# LoginatorCore.net
KiCad netlist of a schematic drawn in EAGLE
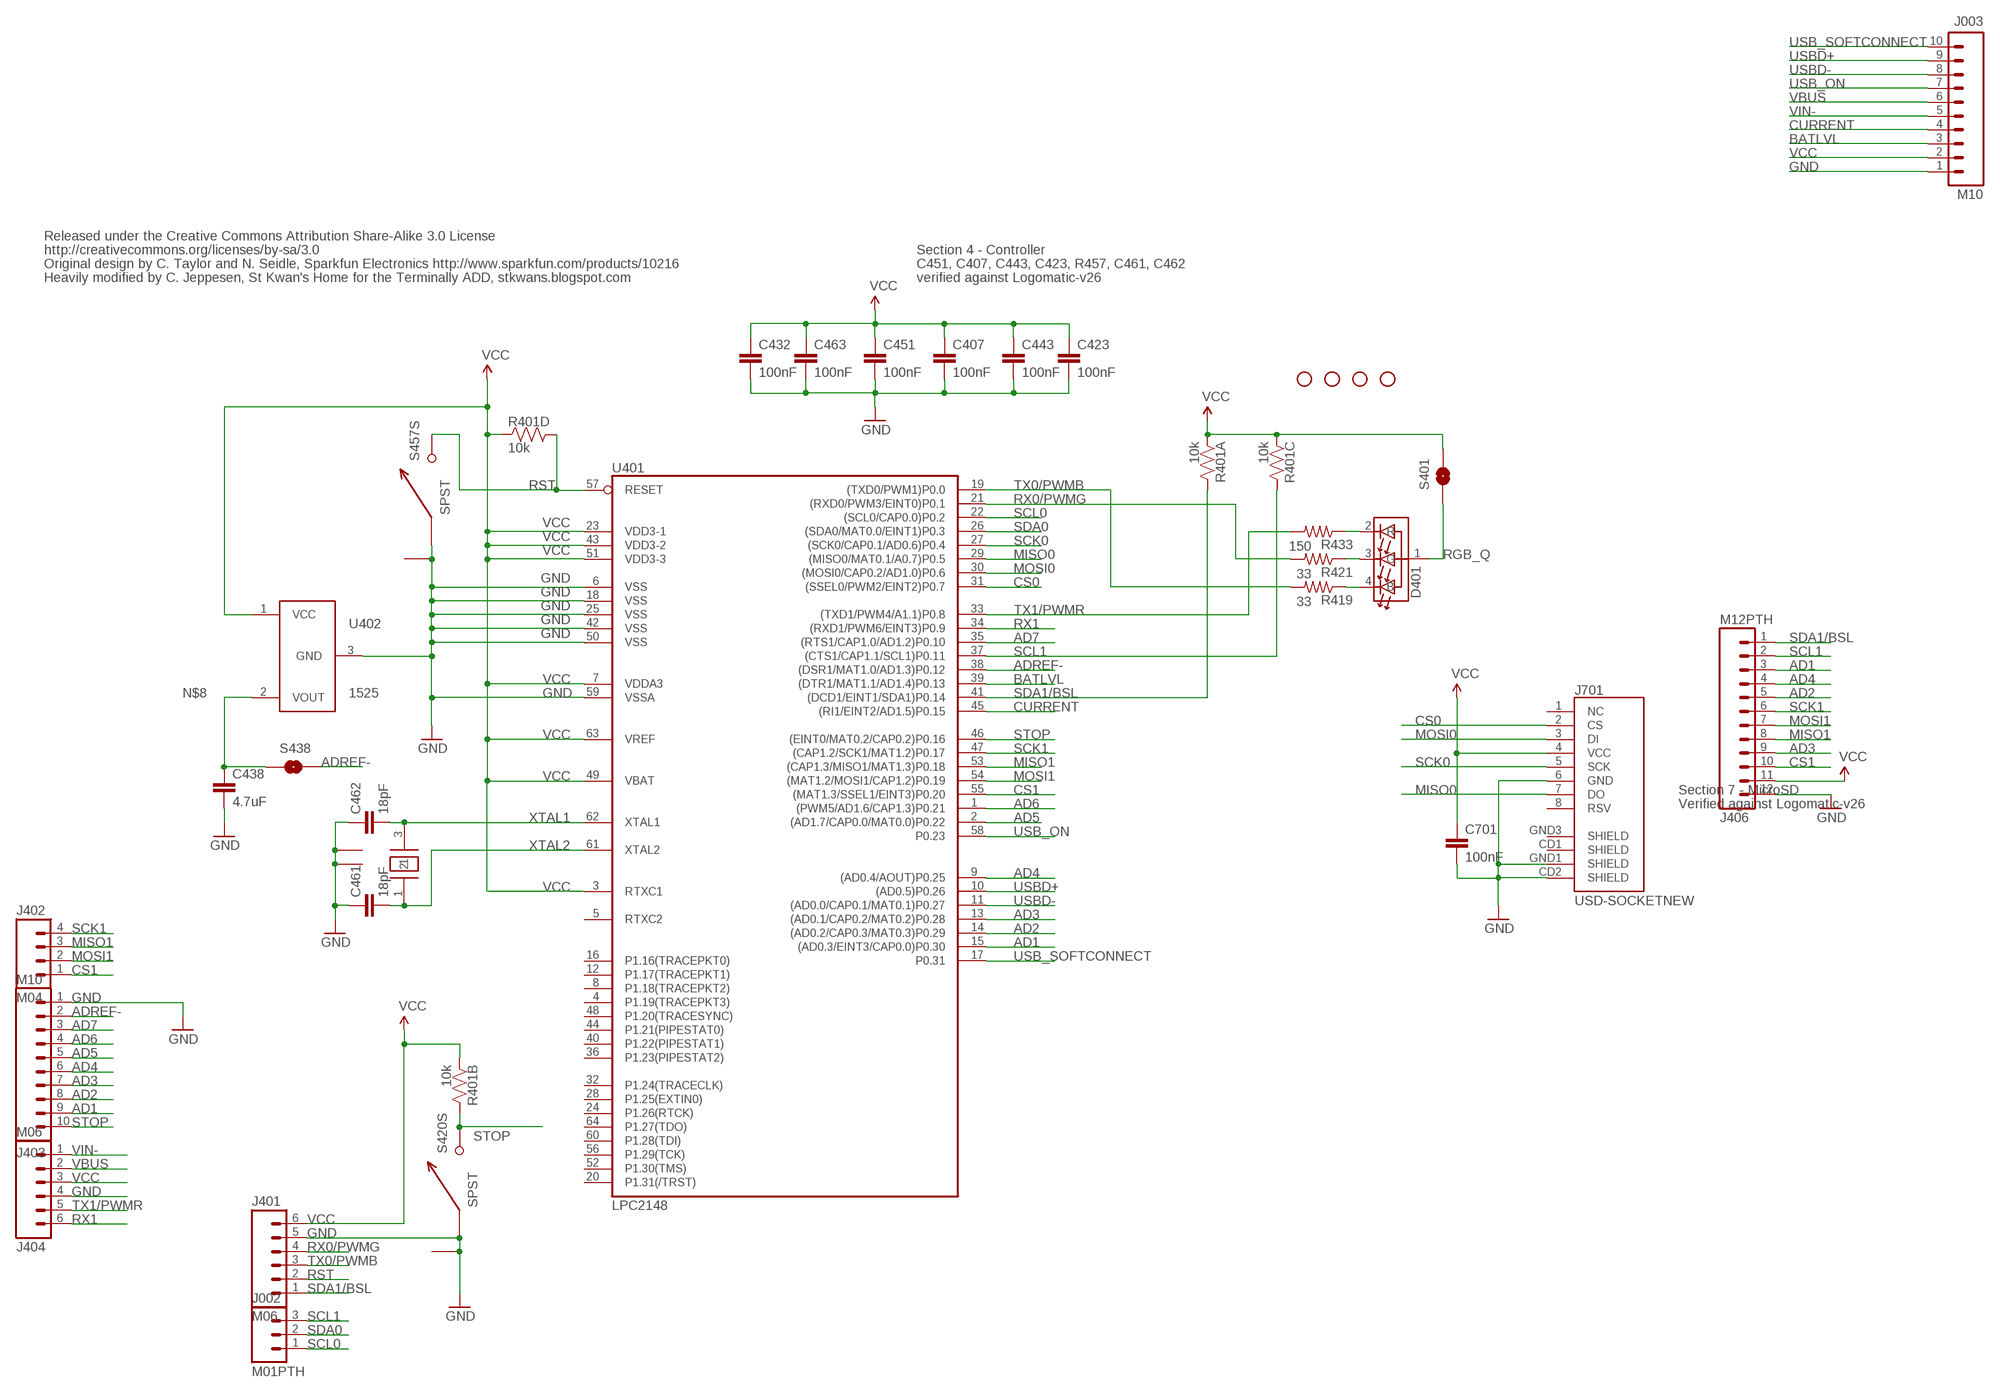
[diagram p0: schematic, sheet 1]

(export (version "E")
  (design (tool "Eeschema 10.0.6"))
  (components
    (comp (ref "C407")
      (value "100nF")
      (footprint "eagle-import:0402-CAP")
      (libsource (lib "eagle-import") (part "CAP0402-CAP"))
    )
    (comp (ref "C423")
      (value "100nF")
      (footprint "eagle-import:0402-CAP")
      (libsource (lib "eagle-import") (part "CAP0402-CAP"))
    )
    (comp (ref "C432")
      (value "100nF")
      (footprint "eagle-import:0402-CAP")
      (libsource (lib "eagle-import") (part "CAP0402-CAP"))
    )
    (comp (ref "C438")
      (value "4.7uF")
      (footprint "eagle-import:0402-CAP")
      (libsource (lib "eagle-import") (part "CAP0402-CAP"))
    )
    (comp (ref "C443")
      (value "100nF")
      (footprint "eagle-import:0402-CAP")
      (libsource (lib "eagle-import") (part "CAP0402-CAP"))
    )
    (comp (ref "C451")
      (value "100nF")
      (footprint "eagle-import:0402-CAP")
      (libsource (lib "eagle-import") (part "CAP0402-CAP"))
    )
    (comp (ref "C461")
      (value "18pF")
      (footprint "eagle-import:0402-CAP")
      (libsource (lib "eagle-import") (part "CAP0402-CAP"))
    )
    (comp (ref "C462")
      (value "18pF")
      (footprint "eagle-import:0402-CAP")
      (libsource (lib "eagle-import") (part "CAP0402-CAP"))
    )
    (comp (ref "C463")
      (value "100nF")
      (footprint "eagle-import:0402-CAP")
      (libsource (lib "eagle-import") (part "CAP0402-CAP"))
    )
    (comp (ref "C701")
      (value "100nF")
      (footprint "eagle-import:0402-CAP")
      (libsource (lib "eagle-import") (part "CAP0402-CAP"))
    )
    (comp (ref "D401")
      (value "HSMF-C118")
      (footprint "eagle-import:HSMF-C118")
      (libsource (lib "eagle-import") (part "HSMF-C118"))
    )
    (comp (ref "J002")
      (value "M01PTH")
      (footprint "eagle-import:1X03")
      (libsource (lib "eagle-import") (part "M03PTH"))
    )
    (comp (ref "J003")
      (value "M10")
      (footprint "eagle-import:1X10")
      (libsource (lib "eagle-import") (part "M10{dblquote}"))
    )
    (comp (ref "J401")
      (value "M06")
      (footprint "eagle-import:1X06")
      (libsource (lib "eagle-import") (part "M06SIP"))
    )
    (comp (ref "J402")
      (value "M04")
      (footprint "eagle-import:1X04")
      (libsource (lib "eagle-import") (part "M04PTH"))
    )
    (comp (ref "J403")
      (value "M10")
      (footprint "eagle-import:1X10")
      (libsource (lib "eagle-import") (part "M10{dblquote}"))
    )
    (comp (ref "J404")
      (value "M06")
      (footprint "eagle-import:1X06")
      (libsource (lib "eagle-import") (part "M06SIP"))
    )
    (comp (ref "J406")
      (value "M12PTH")
      (footprint "eagle-import:1X12")
      (libsource (lib "eagle-import") (part "M12PTH"))
    )
    (comp (ref "J701")
      (value "USD-SOCKETNEW")
      (footprint "eagle-import:MICRO-SD-SOCKET-PP")
      (libsource (lib "eagle-import") (part "USD-SOCKETNEW"))
    )
    (comp (ref "JP1")
      (value "STAND-OFF")
      (footprint "eagle-import:STAND-OFF")
      (libsource (lib "eagle-import") (part "STAND-OFF"))
    )
    (comp (ref "JP2")
      (value "STAND-OFF")
      (footprint "eagle-import:STAND-OFF")
      (libsource (lib "eagle-import") (part "STAND-OFF"))
    )
    (comp (ref "JP3")
      (value "STAND-OFF")
      (footprint "eagle-import:STAND-OFF")
      (libsource (lib "eagle-import") (part "STAND-OFF"))
    )
    (comp (ref "JP4")
      (value "STAND-OFF")
      (footprint "eagle-import:STAND-OFF")
      (libsource (lib "eagle-import") (part "STAND-OFF"))
    )
    (comp (ref "R401")
      (value "10k")
      (footprint "eagle-import:CRA04")
      (libsource (lib "eagle-import") (part "RP404"))
    )
    (comp (ref "R419")
      (value "33")
      (footprint "eagle-import:0402-RES")
      (libsource (lib "eagle-import") (part "RESISTOR0402-RES"))
    )
    (comp (ref "R421")
      (value "33")
      (footprint "eagle-import:0402-RES")
      (libsource (lib "eagle-import") (part "RESISTOR0402-RES"))
    )
    (comp (ref "R433")
      (value "150")
      (footprint "eagle-import:0402-RES")
      (libsource (lib "eagle-import") (part "RESISTOR0402-RES"))
    )
    (comp (ref "S401")
      (value "SOLDERJUMPERNO")
      (footprint "eagle-import:SJ_2S-NO")
      (libsource (lib "eagle-import") (part "SOLDERJUMPERNO"))
    )
    (comp (ref "S420")
      (value "SPST")
      (footprint "eagle-import:B3U-1100P")
      (libsource (lib "eagle-import") (part "B3U-1100P"))
    )
    (comp (ref "S438")
      (value "SOLDERJUMPERNO")
      (footprint "eagle-import:SJ_2S-NO")
      (libsource (lib "eagle-import") (part "SOLDERJUMPERNO"))
    )
    (comp (ref "S457")
      (value "SPST")
      (footprint "eagle-import:B3U-1100P")
      (libsource (lib "eagle-import") (part "B3U-1100P"))
    )
    (comp (ref "U401")
      (value "LPC2148")
      (footprint "eagle-import:SQFP-S-10X10-64")
      (libsource (lib "eagle-import") (part "LPC213X"))
    )
    (comp (ref "U402")
      (value "1525")
      (footprint "eagle-import:SOT-23-3")
      (libsource (lib "eagle-import") (part "MCP1525"))
    )
    (comp (ref "Y401")
      (value "12M")
      (footprint "eagle-import:CRYSTAL_SMD")
      (libsource (lib "eagle-import") (part "TSX-3225"))
    )
  )
  (nets
    (net (code "1") (name "/AD1") (class "Default")
      (node (ref "J403") (pin "9") (pinfunction "9_9") (pintype "passive"))
      (node (ref "J406") (pin "3") (pinfunction "3_3") (pintype "passive"))
      (node (ref "U401") (pin "15") (pinfunction "(AD0.3/EINT3/CAP0.0)P0.30_15") (pintype "bidirectional"))
    )
    (net (code "2") (name "/AD2") (class "Default")
      (node (ref "J403") (pin "8") (pinfunction "8_8") (pintype "passive"))
      (node (ref "J406") (pin "5") (pinfunction "5_5") (pintype "passive"))
      (node (ref "U401") (pin "14") (pinfunction "(AD0.2/CAP0.3/MAT0.3)P0.29_14") (pintype "bidirectional"))
    )
    (net (code "3") (name "/AD3") (class "Default")
      (node (ref "J403") (pin "7") (pinfunction "7_7") (pintype "passive"))
      (node (ref "J406") (pin "9") (pinfunction "9_9") (pintype "passive"))
      (node (ref "U401") (pin "13") (pinfunction "(AD0.1/CAP0.2/MAT0.2)P0.28_13") (pintype "bidirectional"))
    )
    (net (code "4") (name "/AD4") (class "Default")
      (node (ref "J403") (pin "6") (pinfunction "6_6") (pintype "passive"))
      (node (ref "J406") (pin "4") (pinfunction "4_4") (pintype "passive"))
      (node (ref "U401") (pin "9") (pinfunction "(AD0.4/AOUT)P0.25_9") (pintype "bidirectional"))
    )
    (net (code "5") (name "/AD5") (class "Default")
      (node (ref "J403") (pin "5") (pinfunction "5_5") (pintype "passive"))
      (node (ref "U401") (pin "2") (pinfunction "(AD1.7/CAP0.0/MAT0.0)P0.22_2") (pintype "bidirectional"))
    )
    (net (code "6") (name "/AD6") (class "Default")
      (node (ref "J403") (pin "4") (pinfunction "4_4") (pintype "passive"))
      (node (ref "U401") (pin "1") (pinfunction "(PWM5/AD1.6/CAP1.3)P0.21_1") (pintype "bidirectional"))
    )
    (net (code "7") (name "/AD7") (class "Default")
      (node (ref "J403") (pin "3") (pinfunction "3_3") (pintype "passive"))
      (node (ref "U401") (pin "35") (pinfunction "(RTS1/CAP1.0/AD1.2)P0.10_35") (pintype "bidirectional"))
    )
    (net (code "8") (name "/ADREF-") (class "Default")
      (node (ref "J403") (pin "2") (pinfunction "2_2") (pintype "passive"))
      (node (ref "S438") (pin "2") (pinfunction "2_2") (pintype "passive"))
      (node (ref "U401") (pin "38") (pinfunction "(DSR1/MAT1.0/AD1.3)P0.12_38") (pintype "bidirectional"))
    )
    (net (code "9") (name "/BATLVL") (class "Default")
      (node (ref "J003") (pin "3") (pinfunction "3_3") (pintype "passive"))
      (node (ref "U401") (pin "39") (pinfunction "(DTR1/MAT1.1/AD1.4)P0.13_39") (pintype "bidirectional"))
    )
    (net (code "10") (name "/CS0") (class "Default")
      (node (ref "J701") (pin "2") (pinfunction "CS_2") (pintype "bidirectional"))
      (node (ref "U401") (pin "31") (pinfunction "(SSEL0/PWM2/EINT2)P0.7_31") (pintype "bidirectional"))
    )
    (net (code "11") (name "/CS1") (class "Default")
      (node (ref "J402") (pin "1") (pinfunction "1_1") (pintype "passive"))
      (node (ref "J406") (pin "10") (pinfunction "10_10") (pintype "passive"))
      (node (ref "U401") (pin "55") (pinfunction "(MAT1.3/SSEL1/EINT3)P0.20_55") (pintype "bidirectional"))
    )
    (net (code "12") (name "/CURRENT") (class "Default")
      (node (ref "J003") (pin "4") (pinfunction "4_4") (pintype "passive"))
      (node (ref "U401") (pin "45") (pinfunction "(RI1/EINT2/AD1.5)P0.15_45") (pintype "bidirectional"))
    )
    (net (code "13") (name "/MISO0") (class "Default")
      (node (ref "J701") (pin "7") (pinfunction "DO_7") (pintype "bidirectional"))
      (node (ref "U401") (pin "29") (pinfunction "(MISO0/MAT0.1/A0.7)P0.5_29") (pintype "bidirectional"))
    )
    (net (code "14") (name "/MISO1") (class "Default")
      (node (ref "J402") (pin "3") (pinfunction "3_3") (pintype "passive"))
      (node (ref "J406") (pin "8") (pinfunction "8_8") (pintype "passive"))
      (node (ref "U401") (pin "53") (pinfunction "(CAP1.3/MISO1/MAT1.3)P0.18_53") (pintype "bidirectional"))
    )
    (net (code "15") (name "/MOSI0") (class "Default")
      (node (ref "J701") (pin "3") (pinfunction "DI_3") (pintype "bidirectional"))
      (node (ref "U401") (pin "30") (pinfunction "(MOSI0/CAP0.2/AD1.0)P0.6_30") (pintype "bidirectional"))
    )
    (net (code "16") (name "/MOSI1") (class "Default")
      (node (ref "J402") (pin "2") (pinfunction "2_2") (pintype "passive"))
      (node (ref "J406") (pin "7") (pinfunction "7_7") (pintype "passive"))
      (node (ref "U401") (pin "54") (pinfunction "(MAT1.2/MOSI1/CAP1.2)P0.19_54") (pintype "bidirectional"))
    )
    (net (code "17") (name "/N$8") (class "Default")
      (node (ref "C438") (pin "1") (pinfunction "1_1") (pintype "passive"))
      (node (ref "S438") (pin "1") (pinfunction "1_1") (pintype "passive"))
      (node (ref "U402") (pin "2") (pinfunction "VOUT_2") (pintype "bidirectional"))
    )
    (net (code "18") (name "/RGB_Q") (class "Default")
      (node (ref "D401") (pin "1") (pinfunction "A_1") (pintype "passive"))
      (node (ref "S401") (pin "1") (pinfunction "1_1") (pintype "passive"))
    )
    (net (code "19") (name "/RST") (class "Default")
      (node (ref "J401") (pin "2") (pinfunction "2_2") (pintype "passive"))
      (node (ref "R401") (pin "5") (pinfunction "2_5") (pintype "passive"))
      (node (ref "S457") (pin "P$2") (pinfunction "2_P$2") (pintype "bidirectional"))
      (node (ref "U401") (pin "57") (pinfunction "RESET_57") (pintype "input"))
    )
    (net (code "20") (name "/RX0{slash}PWMG") (class "Default")
      (node (ref "J401") (pin "4") (pinfunction "4_4") (pintype "passive"))
      (node (ref "R421") (pin "2") (pinfunction "2_2") (pintype "passive"))
      (node (ref "U401") (pin "21") (pinfunction "(RXD0/PWM3/EINT0)P0.1_21") (pintype "bidirectional"))
    )
    (net (code "21") (name "/RX1") (class "Default")
      (node (ref "J404") (pin "6") (pinfunction "6_6") (pintype "passive"))
      (node (ref "U401") (pin "34") (pinfunction "(RXD1/PWM6/EINT3)P0.9_34") (pintype "bidirectional"))
    )
    (net (code "22") (name "/SCK0") (class "Default")
      (node (ref "J701") (pin "5") (pinfunction "SCK_5") (pintype "bidirectional"))
      (node (ref "U401") (pin "27") (pinfunction "(SCK0/CAP0.1/AD0.6)P0.4_27") (pintype "bidirectional"))
    )
    (net (code "23") (name "/SCK1") (class "Default")
      (node (ref "J402") (pin "4") (pinfunction "4_4") (pintype "passive"))
      (node (ref "J406") (pin "6") (pinfunction "6_6") (pintype "passive"))
      (node (ref "U401") (pin "47") (pinfunction "(CAP1.2/SCK1/MAT1.2)P0.17_47") (pintype "bidirectional"))
    )
    (net (code "24") (name "/SCL0") (class "Default")
      (node (ref "J002") (pin "1") (pinfunction "1_1") (pintype "passive"))
      (node (ref "U401") (pin "22") (pinfunction "(SCL0/CAP0.0)P0.2_22") (pintype "bidirectional"))
    )
    (net (code "25") (name "/SCL1") (class "Default")
      (node (ref "J002") (pin "3") (pinfunction "3_3") (pintype "passive"))
      (node (ref "J406") (pin "2") (pinfunction "2_2") (pintype "passive"))
      (node (ref "R401") (pin "6") (pinfunction "2_6") (pintype "passive"))
      (node (ref "U401") (pin "37") (pinfunction "(CTS1/CAP1.1/SCL1)P0.11_37") (pintype "bidirectional"))
    )
    (net (code "26") (name "/SDA0") (class "Default")
      (node (ref "J002") (pin "2") (pinfunction "2_2") (pintype "passive"))
      (node (ref "U401") (pin "26") (pinfunction "(SDA0/MAT0.0/EINT1)P0.3_26") (pintype "bidirectional"))
    )
    (net (code "27") (name "/SDA1{slash}BSL") (class "Default")
      (node (ref "J401") (pin "1") (pinfunction "1_1") (pintype "passive"))
      (node (ref "J406") (pin "1") (pinfunction "1_1") (pintype "passive"))
      (node (ref "R401") (pin "8") (pinfunction "2_8") (pintype "passive"))
      (node (ref "U401") (pin "41") (pinfunction "(DCD1/EINT1/SDA1)P0.14_41") (pintype "bidirectional"))
    )
    (net (code "28") (name "/STOP") (class "Default")
      (node (ref "J403") (pin "10") (pinfunction "10_10") (pintype "passive"))
      (node (ref "R401") (pin "7") (pinfunction "2_7") (pintype "passive"))
      (node (ref "S420") (pin "P$2") (pinfunction "2_P$2") (pintype "bidirectional"))
      (node (ref "U401") (pin "46") (pinfunction "(EINT0/MAT0.2/CAP0.2)P0.16_46") (pintype "bidirectional"))
    )
    (net (code "29") (name "/TX0{slash}PWMB") (class "Default")
      (node (ref "J401") (pin "3") (pinfunction "3_3") (pintype "passive"))
      (node (ref "R419") (pin "2") (pinfunction "2_2") (pintype "passive"))
      (node (ref "U401") (pin "19") (pinfunction "(TXD0/PWM1)P0.0_19") (pintype "bidirectional"))
    )
    (net (code "30") (name "/TX1{slash}PWMR") (class "Default")
      (node (ref "J404") (pin "5") (pinfunction "5_5") (pintype "passive"))
      (node (ref "R433") (pin "2") (pinfunction "2_2") (pintype "passive"))
      (node (ref "U401") (pin "33") (pinfunction "(TXD1/PWM4/A1.1)P0.8_33") (pintype "bidirectional"))
    )
    (net (code "31") (name "/USBD+") (class "Default")
      (node (ref "J003") (pin "9") (pinfunction "9_9") (pintype "passive"))
      (node (ref "U401") (pin "10") (pinfunction "(AD0.5)P0.26_10") (pintype "bidirectional"))
    )
    (net (code "32") (name "/USBD-") (class "Default")
      (node (ref "J003") (pin "8") (pinfunction "8_8") (pintype "passive"))
      (node (ref "U401") (pin "11") (pinfunction "(AD0.0/CAP0.1/MAT0.1)P0.27_11") (pintype "bidirectional"))
    )
    (net (code "33") (name "/USB_ON") (class "Default")
      (node (ref "J003") (pin "7") (pinfunction "7_7") (pintype "passive"))
      (node (ref "U401") (pin "58") (pinfunction "P0.23_58") (pintype "bidirectional"))
    )
    (net (code "34") (name "/USB_SOFTCONNECT") (class "Default")
      (node (ref "J003") (pin "10") (pinfunction "10_10") (pintype "passive"))
      (node (ref "U401") (pin "17") (pinfunction "P0.31_17") (pintype "output"))
    )
    (net (code "35") (name "/VBUS") (class "Default")
      (node (ref "J003") (pin "6") (pinfunction "6_6") (pintype "passive"))
      (node (ref "J404") (pin "2") (pinfunction "2_2") (pintype "passive"))
    )
    (net (code "36") (name "/VIN-") (class "Default")
      (node (ref "J003") (pin "5") (pinfunction "5_5") (pintype "passive"))
      (node (ref "J404") (pin "1") (pinfunction "1_1") (pintype "passive"))
    )
    (net (code "37") (name "/XTAL1") (class "Default")
      (node (ref "C462") (pin "2") (pinfunction "2_2") (pintype "passive"))
      (node (ref "U401") (pin "62") (pinfunction "XTAL1_62") (pintype "input"))
      (node (ref "Y401") (pin "3") (pinfunction "2_3") (pintype "bidirectional"))
    )
    (net (code "38") (name "/XTAL2") (class "Default")
      (node (ref "C461") (pin "2") (pinfunction "2_2") (pintype "passive"))
      (node (ref "U401") (pin "61") (pinfunction "XTAL2_61") (pintype "output"))
      (node (ref "Y401") (pin "1") (pinfunction "1_1") (pintype "bidirectional"))
    )
    (net (code "39") (name "GND") (class "Default")
      (node (ref "C407") (pin "2") (pinfunction "2_2") (pintype "passive"))
      (node (ref "C423") (pin "2") (pinfunction "2_2") (pintype "passive"))
      (node (ref "C432") (pin "2") (pinfunction "2_2") (pintype "passive"))
      (node (ref "C438") (pin "2") (pinfunction "2_2") (pintype "passive"))
      (node (ref "C443") (pin "2") (pinfunction "2_2") (pintype "passive"))
      (node (ref "C451") (pin "2") (pinfunction "2_2") (pintype "passive"))
      (node (ref "C461") (pin "1") (pinfunction "1_1") (pintype "passive"))
      (node (ref "C462") (pin "1") (pinfunction "1_1") (pintype "passive"))
      (node (ref "C463") (pin "2") (pinfunction "2_2") (pintype "passive"))
      (node (ref "C701") (pin "2") (pinfunction "2_2") (pintype "passive"))
      (node (ref "J003") (pin "1") (pinfunction "1_1") (pintype "passive"))
      (node (ref "J401") (pin "5") (pinfunction "5_5") (pintype "passive"))
      (node (ref "J403") (pin "1") (pinfunction "1_1") (pintype "passive"))
      (node (ref "J404") (pin "4") (pinfunction "4_4") (pintype "passive"))
      (node (ref "J406") (pin "12") (pinfunction "12_12") (pintype "passive"))
      (node (ref "J701") (pin "6") (pinfunction "GND_6") (pintype "bidirectional"))
      (node (ref "J701") (pin "CD2") (pinfunction "SHIELD_CD2") (pintype "bidirectional"))
      (node (ref "J701") (pin "GND1") (pinfunction "SHIELD_GND1") (pintype "bidirectional"))
      (node (ref "S420") (pin "P$1") (pinfunction "1_P$1") (pintype "bidirectional"))
      (node (ref "S420") (pin "P$3") (pinfunction "1_P$3") (pintype "bidirectional"))
      (node (ref "S457") (pin "P$1") (pinfunction "1_P$1") (pintype "bidirectional"))
      (node (ref "S457") (pin "P$3") (pinfunction "1_P$3") (pintype "bidirectional"))
      (node (ref "U401") (pin "18") (pinfunction "VSS_18") (pintype "power_in"))
      (node (ref "U401") (pin "25") (pinfunction "VSS_25") (pintype "power_in"))
      (node (ref "U401") (pin "42") (pinfunction "VSS_42") (pintype "power_in"))
      (node (ref "U401") (pin "50") (pinfunction "VSS_50") (pintype "power_in"))
      (node (ref "U401") (pin "59") (pinfunction "VSSA_59") (pintype "power_in"))
      (node (ref "U401") (pin "6") (pinfunction "VSS_6") (pintype "power_in"))
      (node (ref "U402") (pin "3") (pinfunction "GND_3") (pintype "bidirectional"))
      (node (ref "Y401") (pin "2") (pinfunction "1_2") (pintype "bidirectional"))
      (node (ref "Y401") (pin "4") (pinfunction "1_4") (pintype "bidirectional"))
    )
    (net (code "40") (name "Net-(D401-B)") (class "Default")
      (node (ref "D401") (pin "4") (pinfunction "B_4") (pintype "passive"))
      (node (ref "R419") (pin "1") (pinfunction "1_1") (pintype "passive"))
    )
    (net (code "41") (name "Net-(D401-G)") (class "Default")
      (node (ref "D401") (pin "3") (pinfunction "G_3") (pintype "passive"))
      (node (ref "R421") (pin "1") (pinfunction "1_1") (pintype "passive"))
    )
    (net (code "42") (name "Net-(D401-R)") (class "Default")
      (node (ref "D401") (pin "2") (pinfunction "R_2") (pintype "passive"))
      (node (ref "R433") (pin "1") (pinfunction "1_1") (pintype "passive"))
    )
    (net (code "43") (name "VCC") (class "Default")
      (node (ref "C407") (pin "1") (pinfunction "1_1") (pintype "passive"))
      (node (ref "C423") (pin "1") (pinfunction "1_1") (pintype "passive"))
      (node (ref "C432") (pin "1") (pinfunction "1_1") (pintype "passive"))
      (node (ref "C443") (pin "1") (pinfunction "1_1") (pintype "passive"))
      (node (ref "C451") (pin "1") (pinfunction "1_1") (pintype "passive"))
      (node (ref "C463") (pin "1") (pinfunction "1_1") (pintype "passive"))
      (node (ref "C701") (pin "1") (pinfunction "1_1") (pintype "passive"))
      (node (ref "J003") (pin "2") (pinfunction "2_2") (pintype "passive"))
      (node (ref "J401") (pin "6") (pinfunction "6_6") (pintype "passive"))
      (node (ref "J404") (pin "3") (pinfunction "3_3") (pintype "passive"))
      (node (ref "J406") (pin "11") (pinfunction "11_11") (pintype "passive"))
      (node (ref "J701") (pin "4") (pinfunction "VCC_4") (pintype "bidirectional"))
      (node (ref "R401") (pin "1") (pinfunction "1_1") (pintype "passive"))
      (node (ref "R401") (pin "2") (pinfunction "1_2") (pintype "passive"))
      (node (ref "R401") (pin "3") (pinfunction "1_3") (pintype "passive"))
      (node (ref "R401") (pin "4") (pinfunction "1_4") (pintype "passive"))
      (node (ref "S401") (pin "2") (pinfunction "2_2") (pintype "passive"))
      (node (ref "U401") (pin "23") (pinfunction "VDD3-1_23") (pintype "power_in"))
      (node (ref "U401") (pin "3") (pinfunction "RTXC1_3") (pintype "input"))
      (node (ref "U401") (pin "43") (pinfunction "VDD3-2_43") (pintype "power_in"))
      (node (ref "U401") (pin "49") (pinfunction "VBAT_49") (pintype "power_in"))
      (node (ref "U401") (pin "51") (pinfunction "VDD3-3_51") (pintype "power_in"))
      (node (ref "U401") (pin "63") (pinfunction "VREF_63") (pintype "input"))
      (node (ref "U401") (pin "7") (pinfunction "VDDA3_7") (pintype "power_in"))
      (node (ref "U402") (pin "1") (pinfunction "VCC_1") (pintype "bidirectional"))
    )
    (net (code "44") (name "unconnected-(J701-NC-Pad1)") (class "Default")
      (node (ref "J701") (pin "1") (pinfunction "NC_1") (pintype "bidirectional"))
    )
    (net (code "45") (name "unconnected-(J701-RSV-Pad8)") (class "Default")
      (node (ref "J701") (pin "8") (pinfunction "RSV_8") (pintype "bidirectional"))
    )
    (net (code "46") (name "unconnected-(J701-SHIELD-PadCD1)") (class "Default")
      (node (ref "J701") (pin "CD1") (pinfunction "SHIELD_CD1") (pintype "bidirectional"))
    )
    (net (code "47") (name "unconnected-(J701-SHIELD-PadGND3)") (class "Default")
      (node (ref "J701") (pin "GND3") (pinfunction "SHIELD_GND3") (pintype "bidirectional"))
    )
    (net (code "48") (name "unconnected-(U401-P1.16(TRACEPKT0)-Pad16)") (class "Default")
      (node (ref "U401") (pin "16") (pinfunction "P1.16(TRACEPKT0)_16") (pintype "bidirectional"))
    )
    (net (code "49") (name "unconnected-(U401-P1.17(TRACEPKT1)-Pad12)") (class "Default")
      (node (ref "U401") (pin "12") (pinfunction "P1.17(TRACEPKT1)_12") (pintype "bidirectional"))
    )
    (net (code "50") (name "unconnected-(U401-P1.18(TRACEPKT2)-Pad8)") (class "Default")
      (node (ref "U401") (pin "8") (pinfunction "P1.18(TRACEPKT2)_8") (pintype "bidirectional"))
    )
    (net (code "51") (name "unconnected-(U401-P1.19(TRACEPKT3)-Pad4)") (class "Default")
      (node (ref "U401") (pin "4") (pinfunction "P1.19(TRACEPKT3)_4") (pintype "bidirectional"))
    )
    (net (code "52") (name "unconnected-(U401-P1.20(TRACESYNC)-Pad48)") (class "Default")
      (node (ref "U401") (pin "48") (pinfunction "P1.20(TRACESYNC)_48") (pintype "bidirectional"))
    )
    (net (code "53") (name "unconnected-(U401-P1.21(PIPESTAT0)-Pad44)") (class "Default")
      (node (ref "U401") (pin "44") (pinfunction "P1.21(PIPESTAT0)_44") (pintype "bidirectional"))
    )
    (net (code "54") (name "unconnected-(U401-P1.22(PIPESTAT1)-Pad40)") (class "Default")
      (node (ref "U401") (pin "40") (pinfunction "P1.22(PIPESTAT1)_40") (pintype "bidirectional"))
    )
    (net (code "55") (name "unconnected-(U401-P1.23(PIPESTAT2)-Pad36)") (class "Default")
      (node (ref "U401") (pin "36") (pinfunction "P1.23(PIPESTAT2)_36") (pintype "bidirectional"))
    )
    (net (code "56") (name "unconnected-(U401-P1.24(TRACECLK)-Pad32)") (class "Default")
      (node (ref "U401") (pin "32") (pinfunction "P1.24(TRACECLK)_32") (pintype "bidirectional"))
    )
    (net (code "57") (name "unconnected-(U401-P1.25(EXTIN0)-Pad28)") (class "Default")
      (node (ref "U401") (pin "28") (pinfunction "P1.25(EXTIN0)_28") (pintype "bidirectional"))
    )
    (net (code "58") (name "unconnected-(U401-P1.26(RTCK)-Pad24)") (class "Default")
      (node (ref "U401") (pin "24") (pinfunction "P1.26(RTCK)_24") (pintype "bidirectional"))
    )
    (net (code "59") (name "unconnected-(U401-P1.27(TDO)-Pad64)") (class "Default")
      (node (ref "U401") (pin "64") (pinfunction "P1.27(TDO)_64") (pintype "bidirectional"))
    )
    (net (code "60") (name "unconnected-(U401-P1.28(TDI)-Pad60)") (class "Default")
      (node (ref "U401") (pin "60") (pinfunction "P1.28(TDI)_60") (pintype "bidirectional"))
    )
    (net (code "61") (name "unconnected-(U401-P1.29(TCK)-Pad56)") (class "Default")
      (node (ref "U401") (pin "56") (pinfunction "P1.29(TCK)_56") (pintype "bidirectional"))
    )
    (net (code "62") (name "unconnected-(U401-P1.30(TMS)-Pad52)") (class "Default")
      (node (ref "U401") (pin "52") (pinfunction "P1.30(TMS)_52") (pintype "bidirectional"))
    )
    (net (code "63") (name "unconnected-(U401-P1.31({slash}TRST)-Pad20)") (class "Default")
      (node (ref "U401") (pin "20") (pinfunction "P1.31(/TRST)_20") (pintype "bidirectional"))
    )
    (net (code "64") (name "unconnected-(U401-RTXC2-Pad5)") (class "Default")
      (node (ref "U401") (pin "5") (pinfunction "RTXC2_5") (pintype "output"))
    )
  )
)
